# VIC-20_CHARSET_adapter.net
KiCad netlist of a schematic drawn in EAGLE
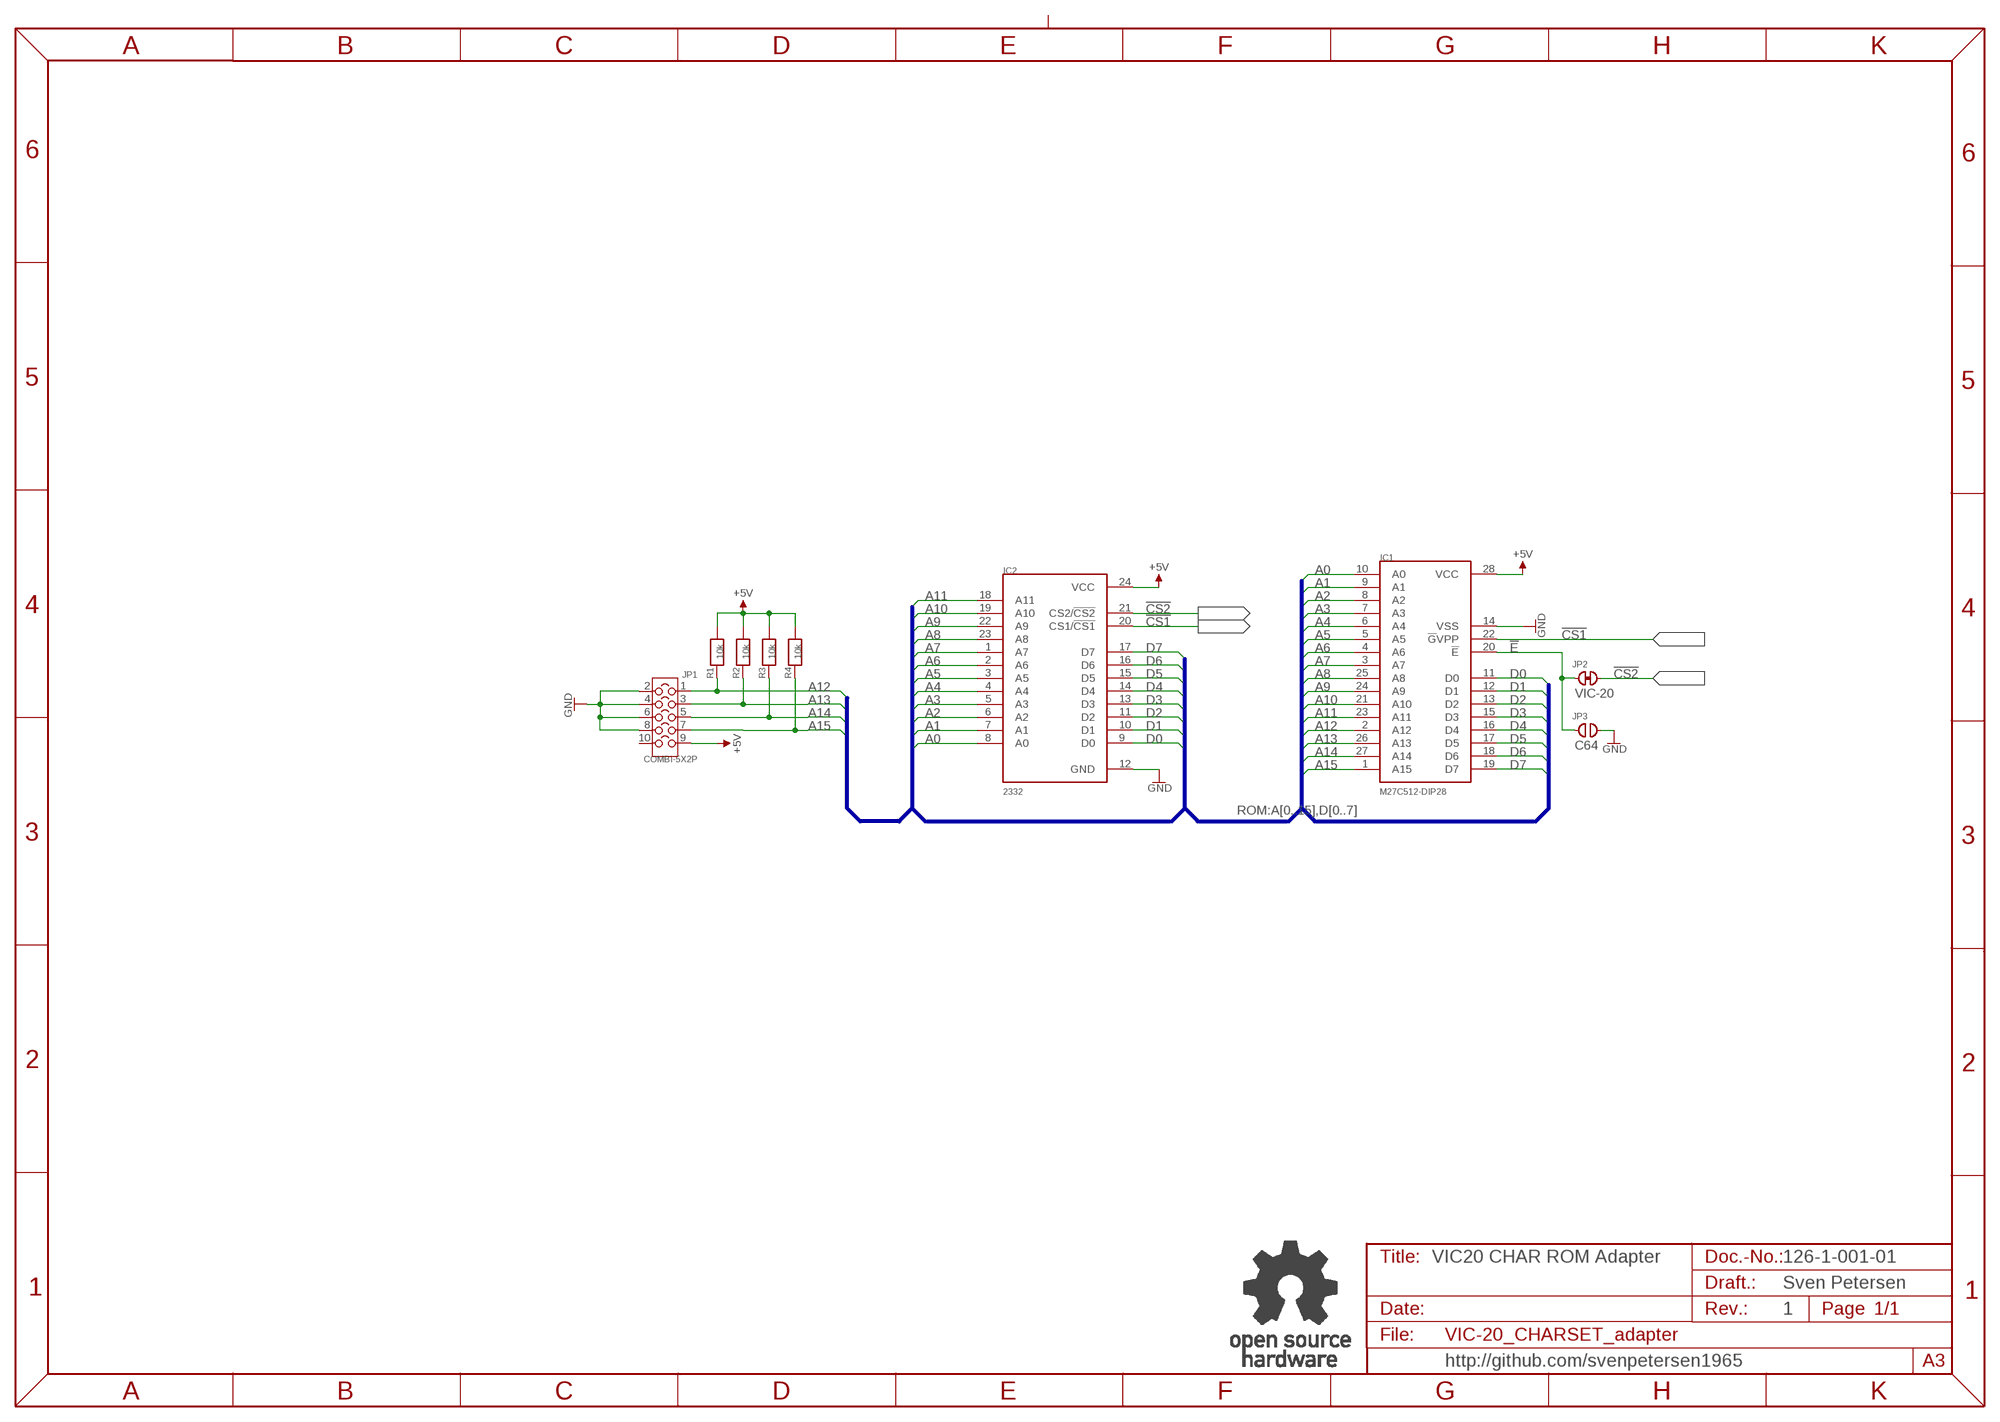
[diagram p0: schematic, sheet 1]

(export (version "E")
  (design (tool "Eeschema 10.0.6"))
  (components
    (comp (ref "IC1")
      (value "M27C512-DIP28")
      (footprint "eagle-import:DIL28-6")
      (libsource (lib "eagle-import") (part "M27C512-DIP28"))
    )
    (comp (ref "IC2")
      (value "2332")
      (footprint "eagle-import:DIL24_SOCKET")
      (libsource (lib "eagle-import") (part "2332"))
    )
    (comp (ref "JP1")
      (value "COMBI-5X2P")
      (footprint "eagle-import:COMBI-5X2")
      (libsource (lib "eagle-import") (part "COMBI-5X2P"))
    )
    (comp (ref "JP2")
      (value "CLOSED")
      (footprint "eagle-import:CP_CL")
      (libsource (lib "eagle-import") (part "CLOSED"))
    )
    (comp (ref "JP3")
      (value "OPEN")
      (footprint "eagle-import:CP_OP")
      (libsource (lib "eagle-import") (part "OPEN"))
    )
    (comp (ref "R1")
      (value "10k")
      (footprint "eagle-import:0805")
      (libsource (lib "eagle-import") (part "R-0805"))
    )
    (comp (ref "R2")
      (value "10k")
      (footprint "eagle-import:0805")
      (libsource (lib "eagle-import") (part "R-0805"))
    )
    (comp (ref "R3")
      (value "10k")
      (footprint "eagle-import:0805")
      (libsource (lib "eagle-import") (part "R-0805"))
    )
    (comp (ref "R4")
      (value "10k")
      (footprint "eagle-import:0805")
      (libsource (lib "eagle-import") (part "R-0805"))
    )
    (comp (ref "U$6")
      (value "OPEN_SOURCE_HW")
      (footprint "eagle-import:OPENHW")
      (libsource (lib "eagle-import") (part "OPEN_SOURCE_HW"))
    )
  )
  (nets
    (net (code "1") (name "+5V") (class "Default")
      (node (ref "IC1") (pin "28") (pinfunction "VCC_28") (pintype "power_in"))
      (node (ref "IC2") (pin "24") (pinfunction "VCC_24") (pintype "power_in"))
      (node (ref "JP1") (pin "9") (pinfunction "9_9") (pintype "bidirectional"))
      (node (ref "R1") (pin "2") (pinfunction "2_2") (pintype "passive"))
      (node (ref "R2") (pin "2") (pinfunction "2_2") (pintype "passive"))
      (node (ref "R3") (pin "2") (pinfunction "2_2") (pintype "passive"))
      (node (ref "R4") (pin "2") (pinfunction "2_2") (pintype "passive"))
    )
    (net (code "2") (name "/A0") (class "Default")
      (node (ref "IC1") (pin "10") (pinfunction "A0_10") (pintype "input"))
      (node (ref "IC2") (pin "8") (pinfunction "A0_8") (pintype "input"))
    )
    (net (code "3") (name "/A1") (class "Default")
      (node (ref "IC1") (pin "9") (pinfunction "A1_9") (pintype "input"))
      (node (ref "IC2") (pin "7") (pinfunction "A1_7") (pintype "input"))
    )
    (net (code "4") (name "/A2") (class "Default")
      (node (ref "IC1") (pin "8") (pinfunction "A2_8") (pintype "input"))
      (node (ref "IC2") (pin "6") (pinfunction "A2_6") (pintype "input"))
    )
    (net (code "5") (name "/A3") (class "Default")
      (node (ref "IC1") (pin "7") (pinfunction "A3_7") (pintype "input"))
      (node (ref "IC2") (pin "5") (pinfunction "A3_5") (pintype "input"))
    )
    (net (code "6") (name "/A4") (class "Default")
      (node (ref "IC1") (pin "6") (pinfunction "A4_6") (pintype "input"))
      (node (ref "IC2") (pin "4") (pinfunction "A4_4") (pintype "input"))
    )
    (net (code "7") (name "/A5") (class "Default")
      (node (ref "IC1") (pin "5") (pinfunction "A5_5") (pintype "input"))
      (node (ref "IC2") (pin "3") (pinfunction "A5_3") (pintype "input"))
    )
    (net (code "8") (name "/A6") (class "Default")
      (node (ref "IC1") (pin "4") (pinfunction "A6_4") (pintype "input"))
      (node (ref "IC2") (pin "2") (pinfunction "A6_2") (pintype "input"))
    )
    (net (code "9") (name "/A7") (class "Default")
      (node (ref "IC1") (pin "3") (pinfunction "A7_3") (pintype "input"))
      (node (ref "IC2") (pin "1") (pinfunction "A7_1") (pintype "input"))
    )
    (net (code "10") (name "/A8") (class "Default")
      (node (ref "IC1") (pin "25") (pinfunction "A8_25") (pintype "input"))
      (node (ref "IC2") (pin "23") (pinfunction "A8_23") (pintype "input"))
    )
    (net (code "11") (name "/A9") (class "Default")
      (node (ref "IC1") (pin "24") (pinfunction "A9_24") (pintype "input"))
      (node (ref "IC2") (pin "22") (pinfunction "A9_22") (pintype "input"))
    )
    (net (code "12") (name "/A10") (class "Default")
      (node (ref "IC1") (pin "21") (pinfunction "A10_21") (pintype "input"))
      (node (ref "IC2") (pin "19") (pinfunction "A10_19") (pintype "input"))
    )
    (net (code "13") (name "/A11") (class "Default")
      (node (ref "IC1") (pin "23") (pinfunction "A11_23") (pintype "input"))
      (node (ref "IC2") (pin "18") (pinfunction "A11_18") (pintype "input"))
    )
    (net (code "14") (name "/A12") (class "Default")
      (node (ref "IC1") (pin "2") (pinfunction "A12_2") (pintype "input"))
      (node (ref "JP1") (pin "1") (pinfunction "1_1") (pintype "bidirectional"))
      (node (ref "R1") (pin "1") (pinfunction "1_1") (pintype "passive"))
    )
    (net (code "15") (name "/A13") (class "Default")
      (node (ref "IC1") (pin "26") (pinfunction "A13_26") (pintype "input"))
      (node (ref "JP1") (pin "3") (pinfunction "3_3") (pintype "bidirectional"))
      (node (ref "R2") (pin "1") (pinfunction "1_1") (pintype "passive"))
    )
    (net (code "16") (name "/A14") (class "Default")
      (node (ref "IC1") (pin "27") (pinfunction "A14_27") (pintype "input"))
      (node (ref "JP1") (pin "5") (pinfunction "5_5") (pintype "bidirectional"))
      (node (ref "R3") (pin "1") (pinfunction "1_1") (pintype "passive"))
    )
    (net (code "17") (name "/A15") (class "Default")
      (node (ref "IC1") (pin "1") (pinfunction "A15_1") (pintype "input"))
      (node (ref "JP1") (pin "7") (pinfunction "7_7") (pintype "bidirectional"))
      (node (ref "R4") (pin "1") (pinfunction "1_1") (pintype "passive"))
    )
    (net (code "18") (name "/D0") (class "Default")
      (node (ref "IC1") (pin "11") (pinfunction "D0_11") (pintype "bidirectional"))
      (node (ref "IC2") (pin "9") (pinfunction "D0_9") (pintype "tri_state"))
    )
    (net (code "19") (name "/D1") (class "Default")
      (node (ref "IC1") (pin "12") (pinfunction "D1_12") (pintype "bidirectional"))
      (node (ref "IC2") (pin "10") (pinfunction "D1_10") (pintype "tri_state"))
    )
    (net (code "20") (name "/D2") (class "Default")
      (node (ref "IC1") (pin "13") (pinfunction "D2_13") (pintype "bidirectional"))
      (node (ref "IC2") (pin "11") (pinfunction "D2_11") (pintype "tri_state"))
    )
    (net (code "21") (name "/D3") (class "Default")
      (node (ref "IC1") (pin "15") (pinfunction "D3_15") (pintype "bidirectional"))
      (node (ref "IC2") (pin "13") (pinfunction "D3_13") (pintype "tri_state"))
    )
    (net (code "22") (name "/D4") (class "Default")
      (node (ref "IC1") (pin "16") (pinfunction "D4_16") (pintype "bidirectional"))
      (node (ref "IC2") (pin "14") (pinfunction "D4_14") (pintype "tri_state"))
    )
    (net (code "23") (name "/D5") (class "Default")
      (node (ref "IC1") (pin "17") (pinfunction "D5_17") (pintype "bidirectional"))
      (node (ref "IC2") (pin "15") (pinfunction "D5_15") (pintype "tri_state"))
    )
    (net (code "24") (name "/D6") (class "Default")
      (node (ref "IC1") (pin "18") (pinfunction "D6_18") (pintype "bidirectional"))
      (node (ref "IC2") (pin "16") (pinfunction "D6_16") (pintype "tri_state"))
    )
    (net (code "25") (name "/D7") (class "Default")
      (node (ref "IC1") (pin "19") (pinfunction "D7_19") (pintype "bidirectional"))
      (node (ref "IC2") (pin "17") (pinfunction "D7_17") (pintype "tri_state"))
    )
    (net (code "27") (name "/~{CS1}") (class "Default")
      (node (ref "IC1") (pin "22") (pinfunction "~{G}VPP_22") (pintype "input"))
      (node (ref "IC2") (pin "20") (pinfunction "CS1/~{CS1}_20") (pintype "input"))
    )
    (net (code "28") (name "/~{CS2}") (class "Default")
      (node (ref "IC2") (pin "21") (pinfunction "CS2/~{CS2}_21") (pintype "input"))
      (node (ref "JP2") (pin "2") (pinfunction "2_2") (pintype "passive"))
    )
    (net (code "29") (name "/~{E}") (class "Default")
      (node (ref "IC1") (pin "20") (pinfunction "~{E}_20") (pintype "input"))
      (node (ref "JP2") (pin "1") (pinfunction "1_1") (pintype "passive"))
      (node (ref "JP3") (pin "1") (pinfunction "1_1") (pintype "passive"))
    )
    (net (code "30") (name "GND") (class "Default")
      (node (ref "IC1") (pin "14") (pinfunction "VSS_14") (pintype "power_in"))
      (node (ref "IC2") (pin "12") (pinfunction "GND_12") (pintype "power_in"))
      (node (ref "JP1") (pin "2") (pinfunction "2_2") (pintype "bidirectional"))
      (node (ref "JP1") (pin "4") (pinfunction "4_4") (pintype "bidirectional"))
      (node (ref "JP1") (pin "6") (pinfunction "6_6") (pintype "bidirectional"))
      (node (ref "JP1") (pin "8") (pinfunction "8_8") (pintype "bidirectional"))
      (node (ref "JP3") (pin "2") (pinfunction "2_2") (pintype "passive"))
    )
    (net (code "31") (name "unconnected-(JP1-Pad10)") (class "Default")
      (node (ref "JP1") (pin "10") (pinfunction "10_10") (pintype "bidirectional"))
    )
  )
)
